# schematicDiagramReceiverBoard.net
KiCad netlist of a schematic drawn in EAGLE
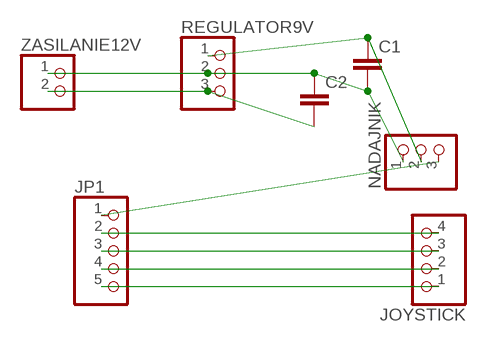
[diagram p0: schematic, sheet 1]

(export (version "E")
  (design (tool "Eeschema 10.0.6"))
  (components
    (comp (ref "C1")
      (value "C2,5-3")
      (footprint "eagle-import:C2.5-3")
      (libsource (lib "eagle-import") (part "C2,5-3"))
    )
    (comp (ref "C2")
      (value "C2,5-3")
      (footprint "eagle-import:C2.5-3")
      (libsource (lib "eagle-import") (part "C2,5-3"))
    )
    (comp (ref "JOYSTICK")
      (value "PINHD-1X4")
      (footprint "eagle-import:1X04")
      (libsource (lib "eagle-import") (part "PINHD-1X4"))
    )
    (comp (ref "JP1")
      (value "PINHD-1X5")
      (footprint "eagle-import:1X05")
      (libsource (lib "eagle-import") (part "PINHD-1X5"))
    )
    (comp (ref "NADAJNIK")
      (value "PINHD-1X3")
      (footprint "eagle-import:1X03")
      (libsource (lib "eagle-import") (part "PINHD-1X3"))
    )
    (comp (ref "REGULATOR9V")
      (value "PINHD-1X3")
      (footprint "eagle-import:1X03")
      (libsource (lib "eagle-import") (part "PINHD-1X3"))
    )
    (comp (ref "ZASILANIE12V")
      (value "PINHD-1X2")
      (footprint "eagle-import:1X02")
      (libsource (lib "eagle-import") (part "PINHD-1X2"))
    )
  )
  (nets
    (net (code "1") (name "Net-(C1-Pad1)") (class "Default")
      (node (ref "C1") (pin "1") (pinfunction "1_1") (pintype "passive"))
      (node (ref "NADAJNIK") (pin "2") (pinfunction "2_2") (pintype "passive"))
      (node (ref "REGULATOR9V") (pin "1") (pinfunction "1_1") (pintype "passive"))
    )
    (net (code "2") (name "Net-(C1-Pad2)") (class "Default")
      (node (ref "C1") (pin "2") (pinfunction "2_2") (pintype "passive"))
      (node (ref "C2") (pin "1") (pinfunction "1_1") (pintype "passive"))
      (node (ref "NADAJNIK") (pin "1") (pinfunction "1_1") (pintype "passive"))
      (node (ref "REGULATOR9V") (pin "2") (pinfunction "2_2") (pintype "passive"))
      (node (ref "ZASILANIE12V") (pin "1") (pinfunction "1_1") (pintype "passive"))
    )
    (net (code "3") (name "Net-(C2-Pad2)") (class "Default")
      (node (ref "C2") (pin "2") (pinfunction "2_2") (pintype "passive"))
      (node (ref "REGULATOR9V") (pin "3") (pinfunction "3_3") (pintype "passive"))
      (node (ref "ZASILANIE12V") (pin "2") (pinfunction "2_2") (pintype "passive"))
    )
    (net (code "4") (name "Net-(JOYSTICK-Pad1)") (class "Default")
      (node (ref "JOYSTICK") (pin "1") (pinfunction "1_1") (pintype "passive"))
      (node (ref "JP1") (pin "5") (pinfunction "5_5") (pintype "passive"))
    )
    (net (code "5") (name "Net-(JOYSTICK-Pad2)") (class "Default")
      (node (ref "JOYSTICK") (pin "2") (pinfunction "2_2") (pintype "passive"))
      (node (ref "JP1") (pin "4") (pinfunction "4_4") (pintype "passive"))
    )
    (net (code "6") (name "Net-(JOYSTICK-Pad3)") (class "Default")
      (node (ref "JOYSTICK") (pin "3") (pinfunction "3_3") (pintype "passive"))
      (node (ref "JP1") (pin "3") (pinfunction "3_3") (pintype "passive"))
    )
    (net (code "7") (name "Net-(JOYSTICK-Pad4)") (class "Default")
      (node (ref "JOYSTICK") (pin "4") (pinfunction "4_4") (pintype "passive"))
      (node (ref "JP1") (pin "2") (pinfunction "2_2") (pintype "passive"))
    )
    (net (code "8") (name "Net-(JP1-Pad1)") (class "Default")
      (node (ref "JP1") (pin "1") (pinfunction "1_1") (pintype "passive"))
      (node (ref "NADAJNIK") (pin "3") (pinfunction "3_3") (pintype "passive"))
    )
  )
)
